# Ethernet.net
KiCad netlist of a schematic drawn in Altium Designer
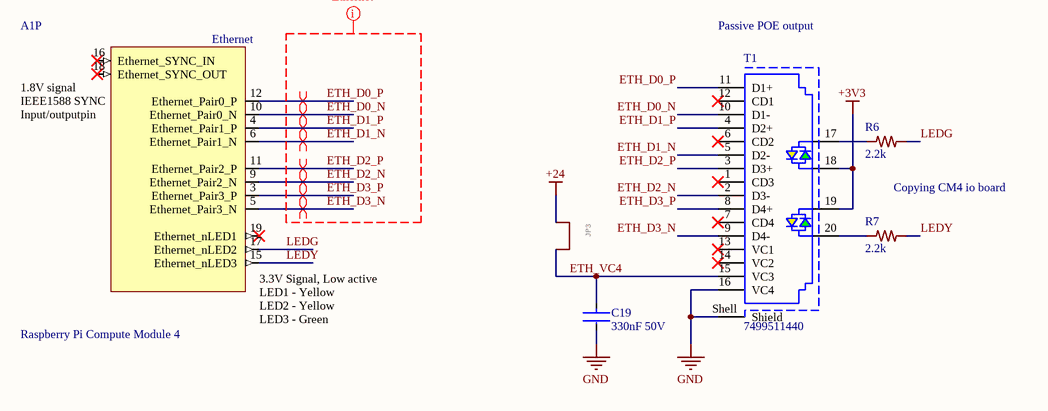
[diagram p0: Ethernet.SchDoc]

(export (version "E")
  (design (tool "Eeschema 10.0.6"))
  (components
    (comp (ref "A1")
      (value "Raspberry Pi Compute Module 4")
      (footprint "CM4-F40C-100DS-0.4v_1.5mm_0mm")
      (description "Raspberry Pi Compute Module 4 by Amornthep Phunsin")
      (libsource (lib "CM4") (part "CM4"))
    )
    (comp (ref "C19")
      (value "330nF 50V")
      (footprint "CAPACITOR_0603")
      (description "CAP CER 0.33UF 50V X7R 0603")
      (fields (field (name "TOLERANCE") "10%") (field (name "VOLTAGE") "50V"))
      (libsource (lib "CM4") (part "C1608X7R1H334K080AC"))
    )
    (comp (ref "JP3")
      (value "TSM-102-01-L-SV")
      (footprint "FP-TSM-102-01-L-SV-P-TR-MFG")
      (description "CONN HEADER SMD 2POS 2.54MM")
      (fields (field (name "MANUFACTURER") "Samtec Inc."))
      (libsource (lib "CM4") (part "JUMPER_?_SMD_2POS"))
    )
    (comp (ref "R6")
      (value "Resistor 0603")
      (footprint "0603R")
      (fields
        (field (name "MPN") "RT0603BRD072K2L")
        (field (name "RESISTANCE") "2.2k")
        (field (name "MFR") "YAGEO")
      )
      (libsource (lib "CM4") (part "RESISTOR_0603"))
    )
    (comp (ref "R7")
      (value "Resistor 0603")
      (footprint "0603R")
      (fields
        (field (name "MPN") "RT0603BRD072K2L")
        (field (name "RESISTANCE") "2.2k")
        (field (name "MFR") "YAGEO")
      )
      (libsource (lib "CM4") (part "RESISTOR_0603"))
    )
    (comp (ref "T1")
      (value "7499511440")
      (footprint "7499511440")
      (description "Telecom and Datacom Connector")
      (fields (field (name "MANUFACTURER") "Wurth Electronics"))
      (libsource (lib "CM4") (part "CMP-03913-30832512-2"))
    )
  )
  (nets
    (net (code "1") (name "+3V3") (class "Default")
      (node (ref "T1") (pin "18") (pinfunction "18_18") (pintype "passive"))
      (node (ref "T1") (pin "19") (pinfunction "19_19") (pintype "passive"))
    )
    (net (code "2") (name "+24") (class "Default")
      (node (ref "JP3") (pin "1") (pinfunction "1_1") (pintype "passive"))
    )
    (net (code "3") (name "/ETH_D0_N") (class "Default")
      (node (ref "A1") (pin "10") (pinfunction "Ethernet_Pair0_N_10") (pintype "passive"))
      (node (ref "T1") (pin "10") (pinfunction "D1-_10") (pintype "passive"))
    )
    (net (code "4") (name "/ETH_D0_P") (class "Default")
      (node (ref "A1") (pin "12") (pinfunction "Ethernet_Pair0_P_12") (pintype "passive"))
      (node (ref "T1") (pin "11") (pinfunction "D1+_11") (pintype "passive"))
    )
    (net (code "5") (name "/ETH_D1_N") (class "Default")
      (node (ref "A1") (pin "6") (pinfunction "Ethernet_Pair1_N_6") (pintype "passive"))
      (node (ref "T1") (pin "5") (pinfunction "D2-_5") (pintype "passive"))
    )
    (net (code "6") (name "/ETH_D1_P") (class "Default")
      (node (ref "A1") (pin "4") (pinfunction "Ethernet_Pair1_P_4") (pintype "passive"))
      (node (ref "T1") (pin "4") (pinfunction "D2+_4") (pintype "passive"))
    )
    (net (code "7") (name "/ETH_D2_N") (class "Default")
      (node (ref "A1") (pin "9") (pinfunction "Ethernet_Pair2_N_9") (pintype "passive"))
      (node (ref "T1") (pin "2") (pinfunction "D3-_2") (pintype "passive"))
    )
    (net (code "8") (name "/ETH_D2_P") (class "Default")
      (node (ref "A1") (pin "11") (pinfunction "Ethernet_Pair2_P_11") (pintype "passive"))
      (node (ref "T1") (pin "3") (pinfunction "D3+_3") (pintype "passive"))
    )
    (net (code "9") (name "/ETH_D3_N") (class "Default")
      (node (ref "A1") (pin "5") (pinfunction "Ethernet_Pair3_N_5") (pintype "passive"))
      (node (ref "T1") (pin "9") (pinfunction "D4-_9") (pintype "passive"))
    )
    (net (code "10") (name "/ETH_D3_P") (class "Default")
      (node (ref "A1") (pin "3") (pinfunction "Ethernet_Pair3_P_3") (pintype "passive"))
      (node (ref "T1") (pin "8") (pinfunction "D4+_8") (pintype "passive"))
    )
    (net (code "11") (name "/ETH_VC4") (class "Default")
      (node (ref "C19") (pin "2") (pinfunction "2_2") (pintype "passive"))
      (node (ref "JP3") (pin "2") (pinfunction "2_2") (pintype "passive"))
      (node (ref "T1") (pin "15") (pinfunction "VC3_15") (pintype "passive"))
    )
    (net (code "12") (name "/LEDG") (class "Default")
      (node (ref "A1") (pin "17") (pinfunction "Ethernet_nLED2_17") (pintype "output"))
      (node (ref "R6") (pin "2") (pinfunction "2_2") (pintype "passive"))
    )
    (net (code "13") (name "/LEDY") (class "Default")
      (node (ref "A1") (pin "15") (pinfunction "Ethernet_nLED3_15") (pintype "output"))
      (node (ref "R7") (pin "2") (pinfunction "2_2") (pintype "passive"))
    )
    (net (code "14") (name "GND") (class "Default")
      (node (ref "C19") (pin "1") (pinfunction "1_1") (pintype "passive"))
      (node (ref "T1") (pin "16") (pinfunction "VC4_16") (pintype "passive"))
      (node (ref "T1") (pin "Shell") (pinfunction "Shield_Shell") (pintype "passive"))
    )
    (net (code "15") (name "Net-(R6-Pad1)") (class "Default")
      (node (ref "R6") (pin "1") (pinfunction "1_1") (pintype "passive"))
      (node (ref "T1") (pin "17") (pinfunction "17_17") (pintype "passive"))
    )
    (net (code "16") (name "Net-(R7-Pad1)") (class "Default")
      (node (ref "R7") (pin "1") (pinfunction "1_1") (pintype "passive"))
      (node (ref "T1") (pin "20") (pinfunction "20_20") (pintype "passive"))
    )
    (net (code "17") (name "unconnected-(A1P-Ethernet_SYNC_IN-Pad16)") (class "Default")
      (node (ref "A1") (pin "16") (pinfunction "Ethernet_SYNC_IN_16") (pintype "input+no_connect"))
    )
    (net (code "18") (name "unconnected-(A1P-Ethernet_SYNC_OUT-Pad18)") (class "Default")
      (node (ref "A1") (pin "18") (pinfunction "Ethernet_SYNC_OUT_18") (pintype "input+no_connect"))
    )
    (net (code "19") (name "unconnected-(A1P-Ethernet_nLED1-Pad19)") (class "Default")
      (node (ref "A1") (pin "19") (pinfunction "Ethernet_nLED1_19") (pintype "output+no_connect"))
    )
    (net (code "20") (name "unconnected-(T1-CD1-Pad12)") (class "Default")
      (node (ref "T1") (pin "12") (pinfunction "CD1_12") (pintype "passive+no_connect"))
    )
    (net (code "21") (name "unconnected-(T1-CD2-Pad6)") (class "Default")
      (node (ref "T1") (pin "6") (pinfunction "CD2_6") (pintype "passive+no_connect"))
    )
    (net (code "22") (name "unconnected-(T1-CD3-Pad1)") (class "Default")
      (node (ref "T1") (pin "1") (pinfunction "CD3_1") (pintype "passive+no_connect"))
    )
    (net (code "23") (name "unconnected-(T1-CD4-Pad7)") (class "Default")
      (node (ref "T1") (pin "7") (pinfunction "CD4_7") (pintype "passive+no_connect"))
    )
    (net (code "24") (name "unconnected-(T1-VC1-Pad13)") (class "Default")
      (node (ref "T1") (pin "13") (pinfunction "VC1_13") (pintype "passive+no_connect"))
    )
    (net (code "25") (name "unconnected-(T1-VC2-Pad14)") (class "Default")
      (node (ref "T1") (pin "14") (pinfunction "VC2_14") (pintype "passive+no_connect"))
    )
  )
)
